# FPGA_MGT.net
KiCad netlist of a schematic drawn in Altium Designer
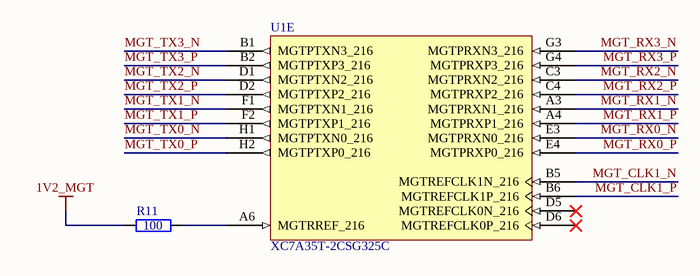
[diagram p0: FPGA_MGT.SchDoc]

(export (version "E")
  (design (tool "Eeschema 10.0.6"))
  (components
    (comp (ref "R11")
      (value "100")
      (footprint "GEN_R_0402")
      (fields (field (name "TOLERANCE") "1%"))
      (libsource (lib "DSO") (part "RES 100 OHM 1% 1/10W 0402"))
    )
    (comp (ref "U1")
      (value "XC7A35T-2CSG325C")
      (footprint "CSG325")
      (description "Artix-7 FPGA, 150 User I/Os, 4 GTP, 324-Ball BGA, Speed Grade 2, Commercial Grade, Pb-Free")
      (fields (field (name "MANUFACTURER") "Xilinx"))
      (libsource (lib "Xilinx Artix-7") (part "XC7A35T-2CSG325C"))
    )
  )
  (nets
    (net (code "1") (name "/MGT_CLK1_N") (class "Default")
      (node (ref "U1") (pin "B5") (pinfunction "MGTREFCLK1N_216_B5") (pintype "input"))
    )
    (net (code "2") (name "/MGT_CLK1_P") (class "Default")
      (node (ref "U1") (pin "B6") (pinfunction "MGTREFCLK1P_216_B6") (pintype "input"))
    )
    (net (code "3") (name "/MGT_RX0_N") (class "Default")
      (node (ref "U1") (pin "E3") (pinfunction "MGTPRXN0_216_E3") (pintype "input"))
    )
    (net (code "4") (name "/MGT_RX0_P") (class "Default")
      (node (ref "U1") (pin "E4") (pinfunction "MGTPRXP0_216_E4") (pintype "input"))
    )
    (net (code "5") (name "/MGT_RX1_N") (class "Default")
      (node (ref "U1") (pin "A3") (pinfunction "MGTPRXN1_216_A3") (pintype "input"))
    )
    (net (code "6") (name "/MGT_RX1_P") (class "Default")
      (node (ref "U1") (pin "A4") (pinfunction "MGTPRXP1_216_A4") (pintype "input"))
    )
    (net (code "7") (name "/MGT_RX2_N") (class "Default")
      (node (ref "U1") (pin "C3") (pinfunction "MGTPRXN2_216_C3") (pintype "input"))
    )
    (net (code "8") (name "/MGT_RX2_P") (class "Default")
      (node (ref "U1") (pin "C4") (pinfunction "MGTPRXP2_216_C4") (pintype "input"))
    )
    (net (code "9") (name "/MGT_RX3_N") (class "Default")
      (node (ref "U1") (pin "G3") (pinfunction "MGTPRXN3_216_G3") (pintype "input"))
    )
    (net (code "10") (name "/MGT_RX3_P") (class "Default")
      (node (ref "U1") (pin "G4") (pinfunction "MGTPRXP3_216_G4") (pintype "input"))
    )
    (net (code "11") (name "/MGT_TX0_N") (class "Default")
      (node (ref "U1") (pin "H1") (pinfunction "MGTPTXN0_216_H1") (pintype "output"))
    )
    (net (code "12") (name "/MGT_TX0_P") (class "Default")
      (node (ref "U1") (pin "H2") (pinfunction "MGTPTXP0_216_H2") (pintype "output"))
    )
    (net (code "13") (name "/MGT_TX1_N") (class "Default")
      (node (ref "U1") (pin "F1") (pinfunction "MGTPTXN1_216_F1") (pintype "output"))
    )
    (net (code "14") (name "/MGT_TX1_P") (class "Default")
      (node (ref "U1") (pin "F2") (pinfunction "MGTPTXP1_216_F2") (pintype "output"))
    )
    (net (code "15") (name "/MGT_TX2_N") (class "Default")
      (node (ref "U1") (pin "D1") (pinfunction "MGTPTXN2_216_D1") (pintype "output"))
    )
    (net (code "16") (name "/MGT_TX2_P") (class "Default")
      (node (ref "U1") (pin "D2") (pinfunction "MGTPTXP2_216_D2") (pintype "output"))
    )
    (net (code "17") (name "/MGT_TX3_N") (class "Default")
      (node (ref "U1") (pin "B1") (pinfunction "MGTPTXN3_216_B1") (pintype "output"))
    )
    (net (code "18") (name "/MGT_TX3_P") (class "Default")
      (node (ref "U1") (pin "B2") (pinfunction "MGTPTXP3_216_B2") (pintype "output"))
    )
    (net (code "19") (name "1V2_MGT") (class "Default")
      (node (ref "R11") (pin "1") (pinfunction "1_1") (pintype "passive"))
    )
    (net (code "20") (name "Net-(U1E-MGTRREF_216)") (class "Default")
      (node (ref "R11") (pin "2") (pinfunction "2_2") (pintype "passive"))
      (node (ref "U1") (pin "A6") (pinfunction "MGTRREF_216_A6") (pintype "input"))
    )
    (net (code "21") (name "unconnected-(U1E-MGTREFCLK0N_216-PadD5)") (class "Default")
      (node (ref "U1") (pin "D5") (pinfunction "MGTREFCLK0N_216_D5") (pintype "input+no_connect"))
    )
    (net (code "22") (name "unconnected-(U1E-MGTREFCLK0P_216-PadD6)") (class "Default")
      (node (ref "U1") (pin "D6") (pinfunction "MGTREFCLK0P_216_D6") (pintype "input+no_connect"))
    )
  )
)
